# Schematic_motor_driver.net
KiCad netlist of a schematic drawn in EAGLE
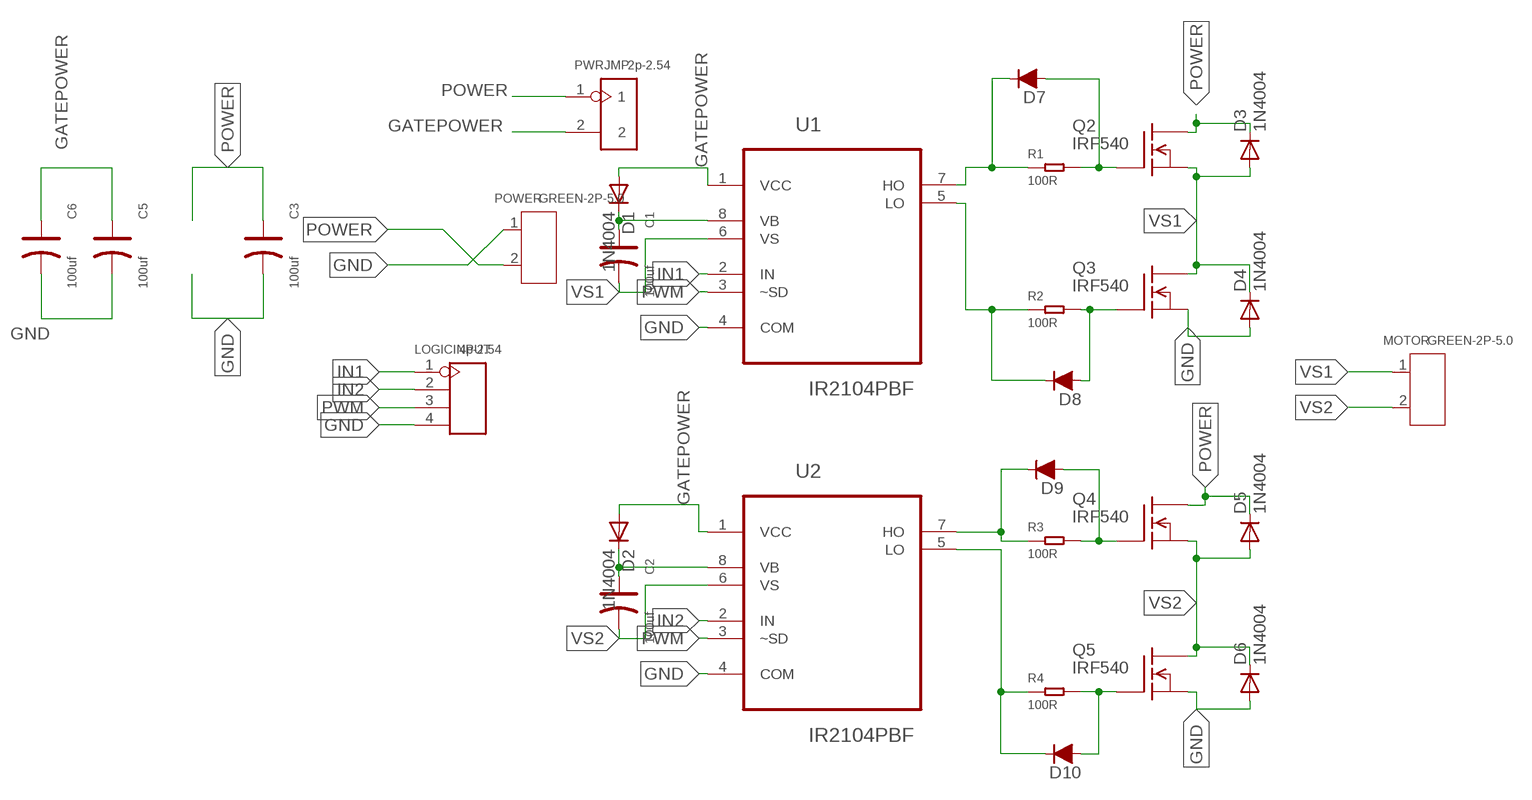
[diagram p0: schematic, sheet 1]

(export (version "E")
  (design (tool "Eeschema 10.0.6"))
  (components
    (comp (ref "C1")
      (value "100uf")
      (footprint "eagle-import:PC-D5.3MM")
      (fields (field (name "MPN") "KS 100uF/16V"))
      (libsource (lib "eagle-import") (part "DIP-ALUMINUM-100UF-16V(D5-H7MM)"))
    )
    (comp (ref "C2")
      (value "100uf")
      (footprint "eagle-import:PC-D5.3MM")
      (fields (field (name "MPN") "KS 100uF/16V"))
      (libsource (lib "eagle-import") (part "DIP-ALUMINUM-100UF-16V(D5-H7MM)"))
    )
    (comp (ref "C3")
      (value "100uf")
      (footprint "eagle-import:PC-D5.3MM")
      (fields (field (name "MPN") "KS 100uF/16V"))
      (libsource (lib "eagle-import") (part "DIP-ALUMINUM-100UF-16V(D5-H7MM)"))
    )
    (comp (ref "C5")
      (value "100uf")
      (footprint "eagle-import:PC-D5.3MM")
      (fields (field (name "MPN") "KS 100uF/16V"))
      (libsource (lib "eagle-import") (part "DIP-ALUMINUM-100UF-16V(D5-H7MM)"))
    )
    (comp (ref "C6")
      (value "100uf")
      (footprint "eagle-import:PC-D5.3MM")
      (fields (field (name "MPN") "KS 100uF/16V"))
      (libsource (lib "eagle-import") (part "DIP-ALUMINUM-100UF-16V(D5-H7MM)"))
    )
    (comp (ref "D1")
      (value "1N4004")
      (footprint "eagle-import:DO41-10")
      (libsource (lib "eagle-import") (part "1N4004"))
    )
    (comp (ref "D2")
      (value "1N4004")
      (footprint "eagle-import:DO41-10")
      (libsource (lib "eagle-import") (part "1N4004"))
    )
    (comp (ref "D3")
      (value "1N4004")
      (footprint "eagle-import:DO41-10")
      (libsource (lib "eagle-import") (part "1N4004"))
    )
    (comp (ref "D4")
      (value "1N4004")
      (footprint "eagle-import:DO41-10")
      (libsource (lib "eagle-import") (part "1N4004"))
    )
    (comp (ref "D5")
      (value "1N4004")
      (footprint "eagle-import:DO41-10")
      (libsource (lib "eagle-import") (part "1N4004"))
    )
    (comp (ref "D6")
      (value "1N4004")
      (footprint "eagle-import:DO41-10")
      (libsource (lib "eagle-import") (part "1N4004"))
    )
    (comp (ref "D7")
      (value "D-FILL-MLL-41")
      (footprint "eagle-import:MELF-MLL41")
      (libsource (lib "eagle-import") (part "D-FILL-MLL-41"))
    )
    (comp (ref "D8")
      (value "D-FILL-MLL-41")
      (footprint "eagle-import:MELF-MLL41")
      (libsource (lib "eagle-import") (part "D-FILL-MLL-41"))
    )
    (comp (ref "D9")
      (value "D-FILL-MLL-41")
      (footprint "eagle-import:MELF-MLL41")
      (libsource (lib "eagle-import") (part "D-FILL-MLL-41"))
    )
    (comp (ref "D10")
      (value "D-FILL-MLL-41")
      (footprint "eagle-import:MELF-MLL41")
      (libsource (lib "eagle-import") (part "D-FILL-MLL-41"))
    )
    (comp (ref "LOGICINPUT")
      (value "4p-2.54")
      (footprint "eagle-import:H4-2.54")
      (fields (field (name "MPN") "F185-1104A1BSYA1"))
      (libsource (lib "eagle-import") (part "DIP-BLACK-FEMALE-HEADER-VERT(4P-2.54)"))
    )
    (comp (ref "MOTOR")
      (value "GREEN-2P-5.0")
      (footprint "eagle-import:H2-5.0-10.5X8.0MM")
      (libsource (lib "eagle-import") (part "SCREW-TERMINAL-GREEN(2P-5.0)"))
    )
    (comp (ref "POWER")
      (value "GREEN-2P-5.0")
      (footprint "eagle-import:H2-5.0-10.5X8.0MM")
      (libsource (lib "eagle-import") (part "SCREW-TERMINAL-GREEN(2P-5.0)"))
    )
    (comp (ref "PWRJMP")
      (value "2p-2.54")
      (footprint "eagle-import:H2-2.54")
      (fields (field (name "MPN") "P125-1102A0BS116A1"))
      (libsource (lib "eagle-import") (part "DIP-BLACK-MALE-HEADER-VERT(2P-2.54)"))
    )
    (comp (ref "Q2")
      (value "IRF540")
      (footprint "eagle-import:TO220")
      (libsource (lib "eagle-import") (part "IRF540"))
    )
    (comp (ref "Q3")
      (value "IRF540")
      (footprint "eagle-import:TO220")
      (libsource (lib "eagle-import") (part "IRF540"))
    )
    (comp (ref "Q4")
      (value "IRF540")
      (footprint "eagle-import:TO220")
      (libsource (lib "eagle-import") (part "IRF540"))
    )
    (comp (ref "Q5")
      (value "IRF540")
      (footprint "eagle-import:TO220")
      (libsource (lib "eagle-import") (part "IRF540"))
    )
    (comp (ref "R1")
      (value "100R")
      (footprint "eagle-import:R1206")
      (fields (field (name "MPN") "RC1206JR-07100RL"))
      (libsource (lib "eagle-import") (part "SMD-RES-100R-5%-1/4W(1206)"))
    )
    (comp (ref "R2")
      (value "100R")
      (footprint "eagle-import:R1206")
      (fields (field (name "MPN") "RC1206JR-07100RL"))
      (libsource (lib "eagle-import") (part "SMD-RES-100R-5%-1/4W(1206)"))
    )
    (comp (ref "R3")
      (value "100R")
      (footprint "eagle-import:R1206")
      (fields (field (name "MPN") "RC1206JR-07100RL"))
      (libsource (lib "eagle-import") (part "SMD-RES-100R-5%-1/4W(1206)"))
    )
    (comp (ref "R4")
      (value "100R")
      (footprint "eagle-import:R1206")
      (fields (field (name "MPN") "RC1206JR-07100RL"))
      (libsource (lib "eagle-import") (part "SMD-RES-100R-5%-1/4W(1206)"))
    )
    (comp (ref "U1")
      (value "IR2104PBF")
      (footprint "eagle-import:DIP254P762X533-8")
      (libsource (lib "eagle-import") (part "IR2104PBF"))
    )
    (comp (ref "U2")
      (value "IR2104PBF")
      (footprint "eagle-import:DIP254P762X533-8")
      (libsource (lib "eagle-import") (part "IR2104PBF"))
    )
  )
  (nets
    (net (code "1") (name "/GATEPOWER") (class "Default")
      (node (ref "C5") (pin "+") (pinfunction "+_+") (pintype "passive"))
      (node (ref "C6") (pin "+") (pinfunction "+_+") (pintype "passive"))
      (node (ref "D1") (pin "A") (pinfunction "A_A") (pintype "passive"))
      (node (ref "D2") (pin "A") (pinfunction "A_A") (pintype "passive"))
      (node (ref "PWRJMP") (pin "2") (pinfunction "2_2") (pintype "bidirectional"))
      (node (ref "U1") (pin "1") (pinfunction "VCC_1") (pintype "power_in"))
      (node (ref "U2") (pin "1") (pinfunction "VCC_1") (pintype "power_in"))
    )
    (net (code "2") (name "GND") (class "Default")
      (node (ref "C3") (pin "-") (pinfunction "-_-") (pintype "passive"))
      (node (ref "C5") (pin "-") (pinfunction "-_-") (pintype "passive"))
      (node (ref "C6") (pin "-") (pinfunction "-_-") (pintype "passive"))
      (node (ref "D4") (pin "A") (pinfunction "A_A") (pintype "passive"))
      (node (ref "D6") (pin "A") (pinfunction "A_A") (pintype "passive"))
      (node (ref "LOGICINPUT") (pin "4") (pinfunction "P$4_4") (pintype "bidirectional"))
      (node (ref "POWER") (pin "1") (pinfunction "1_1") (pintype "bidirectional"))
      (node (ref "Q3") (pin "3") (pinfunction "S_3") (pintype "passive"))
      (node (ref "Q5") (pin "3") (pinfunction "S_3") (pintype "passive"))
      (node (ref "U1") (pin "4") (pinfunction "COM_4") (pintype "input"))
      (node (ref "U2") (pin "4") (pinfunction "COM_4") (pintype "input"))
    )
    (net (code "3") (name "IN1") (class "Default")
      (node (ref "LOGICINPUT") (pin "1") (pinfunction "P$1_1") (pintype "bidirectional"))
      (node (ref "U1") (pin "2") (pinfunction "IN_2") (pintype "input"))
    )
    (net (code "4") (name "IN2") (class "Default")
      (node (ref "LOGICINPUT") (pin "2") (pinfunction "P$2_2") (pintype "bidirectional"))
      (node (ref "U2") (pin "2") (pinfunction "IN_2") (pintype "input"))
    )
    (net (code "5") (name "Net-(D7-A)") (class "Default")
      (node (ref "D7") (pin "2") (pinfunction "A_2") (pintype "passive"))
      (node (ref "Q2") (pin "1") (pinfunction "G_1") (pintype "passive"))
      (node (ref "R1") (pin "2") (pinfunction "2_2") (pintype "passive"))
    )
    (net (code "6") (name "Net-(D7-C)") (class "Default")
      (node (ref "D7") (pin "1") (pinfunction "C_1") (pintype "passive"))
      (node (ref "R1") (pin "1") (pinfunction "1_1") (pintype "passive"))
      (node (ref "U1") (pin "7") (pinfunction "HO_7") (pintype "output"))
    )
    (net (code "7") (name "Net-(D8-A)") (class "Default")
      (node (ref "D8") (pin "2") (pinfunction "A_2") (pintype "passive"))
      (node (ref "Q3") (pin "1") (pinfunction "G_1") (pintype "passive"))
      (node (ref "R2") (pin "2") (pinfunction "2_2") (pintype "passive"))
    )
    (net (code "8") (name "Net-(D8-C)") (class "Default")
      (node (ref "D8") (pin "1") (pinfunction "C_1") (pintype "passive"))
      (node (ref "R2") (pin "1") (pinfunction "1_1") (pintype "passive"))
      (node (ref "U1") (pin "5") (pinfunction "LO_5") (pintype "output"))
    )
    (net (code "9") (name "Net-(D9-A)") (class "Default")
      (node (ref "D9") (pin "2") (pinfunction "A_2") (pintype "passive"))
      (node (ref "Q4") (pin "1") (pinfunction "G_1") (pintype "passive"))
      (node (ref "R3") (pin "2") (pinfunction "2_2") (pintype "passive"))
    )
    (net (code "10") (name "Net-(D9-C)") (class "Default")
      (node (ref "D9") (pin "1") (pinfunction "C_1") (pintype "passive"))
      (node (ref "R3") (pin "1") (pinfunction "1_1") (pintype "passive"))
      (node (ref "U2") (pin "7") (pinfunction "HO_7") (pintype "output"))
    )
    (net (code "11") (name "Net-(D10-A)") (class "Default")
      (node (ref "D10") (pin "2") (pinfunction "A_2") (pintype "passive"))
      (node (ref "Q5") (pin "1") (pinfunction "G_1") (pintype "passive"))
      (node (ref "R4") (pin "2") (pinfunction "2_2") (pintype "passive"))
    )
    (net (code "12") (name "Net-(D10-C)") (class "Default")
      (node (ref "D10") (pin "1") (pinfunction "C_1") (pintype "passive"))
      (node (ref "R4") (pin "1") (pinfunction "1_1") (pintype "passive"))
      (node (ref "U2") (pin "5") (pinfunction "LO_5") (pintype "output"))
    )
    (net (code "13") (name "Net-(U1-VB)") (class "Default")
      (node (ref "C1") (pin "+") (pinfunction "+_+") (pintype "passive"))
      (node (ref "D1") (pin "C") (pinfunction "C_C") (pintype "passive"))
      (node (ref "U1") (pin "8") (pinfunction "VB_8") (pintype "power_in"))
    )
    (net (code "14") (name "Net-(U2-VB)") (class "Default")
      (node (ref "C2") (pin "+") (pinfunction "+_+") (pintype "passive"))
      (node (ref "D2") (pin "C") (pinfunction "C_C") (pintype "passive"))
      (node (ref "U2") (pin "8") (pinfunction "VB_8") (pintype "power_in"))
    )
    (net (code "15") (name "POWER") (class "Default")
      (node (ref "C3") (pin "+") (pinfunction "+_+") (pintype "passive"))
      (node (ref "D3") (pin "C") (pinfunction "C_C") (pintype "passive"))
      (node (ref "D5") (pin "C") (pinfunction "C_C") (pintype "passive"))
      (node (ref "POWER") (pin "2") (pinfunction "2_2") (pintype "bidirectional"))
      (node (ref "PWRJMP") (pin "1") (pinfunction "1_1") (pintype "bidirectional"))
      (node (ref "Q2") (pin "2") (pinfunction "D_2") (pintype "passive"))
      (node (ref "Q4") (pin "2") (pinfunction "D_2") (pintype "passive"))
    )
    (net (code "16") (name "PWM") (class "Default")
      (node (ref "LOGICINPUT") (pin "3") (pinfunction "P$3_3") (pintype "bidirectional"))
      (node (ref "U1") (pin "3") (pinfunction "~{SD}_3") (pintype "input"))
      (node (ref "U2") (pin "3") (pinfunction "~{SD}_3") (pintype "input"))
    )
    (net (code "17") (name "VS1") (class "Default")
      (node (ref "C1") (pin "-") (pinfunction "-_-") (pintype "passive"))
      (node (ref "D3") (pin "A") (pinfunction "A_A") (pintype "passive"))
      (node (ref "D4") (pin "C") (pinfunction "C_C") (pintype "passive"))
      (node (ref "MOTOR") (pin "1") (pinfunction "1_1") (pintype "bidirectional"))
      (node (ref "Q2") (pin "3") (pinfunction "S_3") (pintype "passive"))
      (node (ref "Q3") (pin "2") (pinfunction "D_2") (pintype "passive"))
      (node (ref "U1") (pin "6") (pinfunction "VS_6") (pintype "power_in"))
    )
    (net (code "18") (name "VS2") (class "Default")
      (node (ref "C2") (pin "-") (pinfunction "-_-") (pintype "passive"))
      (node (ref "D5") (pin "A") (pinfunction "A_A") (pintype "passive"))
      (node (ref "D6") (pin "C") (pinfunction "C_C") (pintype "passive"))
      (node (ref "MOTOR") (pin "2") (pinfunction "2_2") (pintype "bidirectional"))
      (node (ref "Q4") (pin "3") (pinfunction "S_3") (pintype "passive"))
      (node (ref "Q5") (pin "2") (pinfunction "D_2") (pintype "passive"))
      (node (ref "U2") (pin "6") (pinfunction "VS_6") (pintype "power_in"))
    )
  )
)
